# RP5_Right_Flex.net
KiCad netlist of a schematic drawn in Altium Designer
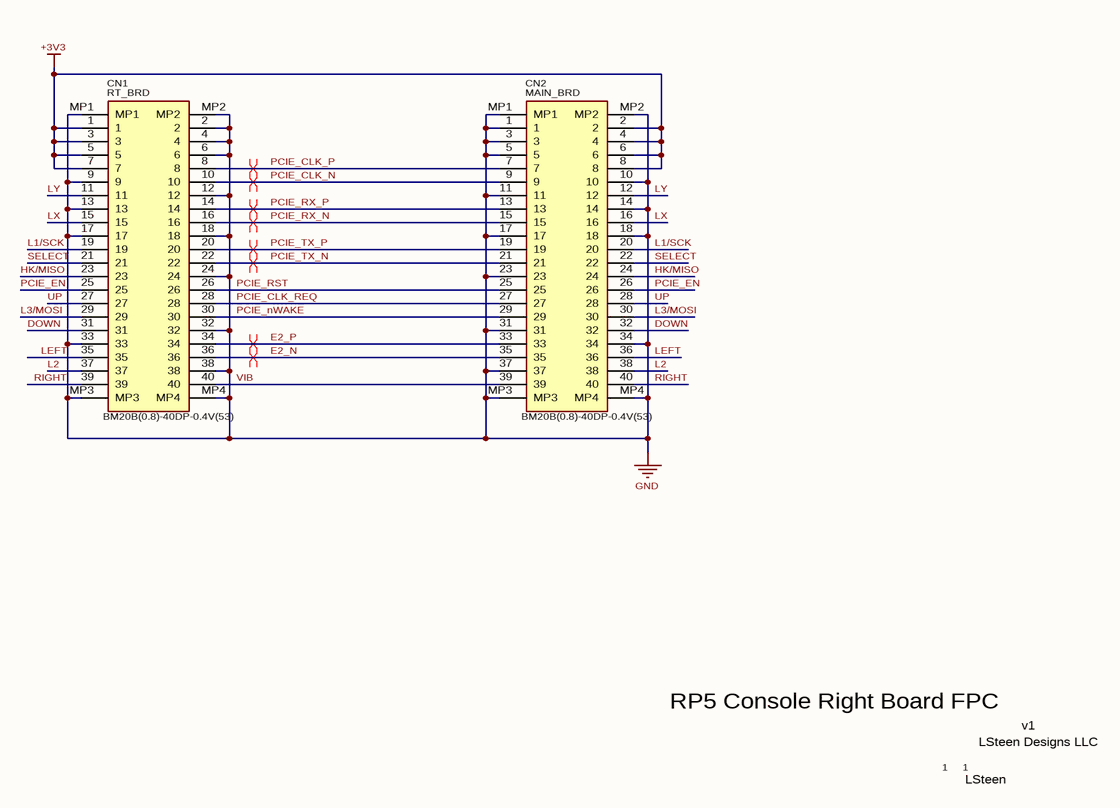
[diagram p0: RP5_Right_Flex.SchDoc]

(export (version "E")
  (design (tool "Eeschema 10.0.6"))
  (components
    (comp (ref "CN1")
      (value "RT_BRD")
      (footprint "BM20B0840DP04V53")
      (description "Connector")
      (fields (field (name "MANUFACTURER_PART_NUMBER") "BM20B(0.8)-40DP-0.4V(51)"))
      (libsource (lib "SamacSys") (part "BM20B(0.8)-40DP-0.4V(53)"))
    )
    (comp (ref "CN2")
      (value "MAIN_BRD")
      (footprint "BM20B0840DP04V53")
      (description "Connector")
      (fields (field (name "MANUFACTURER_PART_NUMBER") "BM20B(0.8)-40DP-0.4V(51)"))
      (libsource (lib "SamacSys") (part "BM20B(0.8)-40DP-0.4V(53)"))
    )
  )
  (nets
    (net (code "1") (name "+3V3") (class "Default")
      (node (ref "CN1") (pin "1") (pinfunction "1_1") (pintype "passive"))
      (node (ref "CN1") (pin "3") (pinfunction "3_3") (pintype "passive"))
      (node (ref "CN1") (pin "5") (pinfunction "5_5") (pintype "passive"))
      (node (ref "CN1") (pin "7") (pinfunction "7_7") (pintype "passive"))
      (node (ref "CN2") (pin "2") (pinfunction "2_2") (pintype "passive"))
      (node (ref "CN2") (pin "4") (pinfunction "4_4") (pintype "passive"))
      (node (ref "CN2") (pin "6") (pinfunction "6_6") (pintype "passive"))
      (node (ref "CN2") (pin "8") (pinfunction "8_8") (pintype "passive"))
    )
    (net (code "2") (name "/DOWN") (class "Default")
      (node (ref "CN1") (pin "31") (pinfunction "31_31") (pintype "passive"))
      (node (ref "CN2") (pin "32") (pinfunction "32_32") (pintype "passive"))
    )
    (net (code "3") (name "/E2_N") (class "Default")
      (node (ref "CN1") (pin "36") (pinfunction "36_36") (pintype "passive"))
      (node (ref "CN2") (pin "35") (pinfunction "35_35") (pintype "passive"))
    )
    (net (code "4") (name "/E2_P") (class "Default")
      (node (ref "CN1") (pin "34") (pinfunction "34_34") (pintype "passive"))
      (node (ref "CN2") (pin "33") (pinfunction "33_33") (pintype "passive"))
    )
    (net (code "5") (name "/HK{slash}MISO") (class "Default")
      (node (ref "CN1") (pin "23") (pinfunction "23_23") (pintype "passive"))
      (node (ref "CN2") (pin "24") (pinfunction "24_24") (pintype "passive"))
    )
    (net (code "6") (name "/L1{slash}SCK") (class "Default")
      (node (ref "CN1") (pin "19") (pinfunction "19_19") (pintype "passive"))
      (node (ref "CN2") (pin "20") (pinfunction "20_20") (pintype "passive"))
    )
    (net (code "7") (name "/L2") (class "Default")
      (node (ref "CN1") (pin "37") (pinfunction "37_37") (pintype "passive"))
      (node (ref "CN2") (pin "38") (pinfunction "38_38") (pintype "passive"))
    )
    (net (code "8") (name "/L3{slash}MOSI") (class "Default")
      (node (ref "CN1") (pin "29") (pinfunction "29_29") (pintype "passive"))
      (node (ref "CN2") (pin "30") (pinfunction "30_30") (pintype "passive"))
    )
    (net (code "9") (name "/LEFT") (class "Default")
      (node (ref "CN1") (pin "35") (pinfunction "35_35") (pintype "passive"))
      (node (ref "CN2") (pin "36") (pinfunction "36_36") (pintype "passive"))
    )
    (net (code "10") (name "/LX") (class "Default")
      (node (ref "CN1") (pin "15") (pinfunction "15_15") (pintype "passive"))
      (node (ref "CN2") (pin "16") (pinfunction "16_16") (pintype "passive"))
    )
    (net (code "11") (name "/LY") (class "Default")
      (node (ref "CN1") (pin "11") (pinfunction "11_11") (pintype "passive"))
      (node (ref "CN2") (pin "12") (pinfunction "12_12") (pintype "passive"))
    )
    (net (code "12") (name "/PCIE_CLK_N") (class "Default")
      (node (ref "CN1") (pin "10") (pinfunction "10_10") (pintype "passive"))
      (node (ref "CN2") (pin "9") (pinfunction "9_9") (pintype "passive"))
    )
    (net (code "13") (name "/PCIE_CLK_P") (class "Default")
      (node (ref "CN1") (pin "8") (pinfunction "8_8") (pintype "passive"))
      (node (ref "CN2") (pin "7") (pinfunction "7_7") (pintype "passive"))
    )
    (net (code "14") (name "/PCIE_CLK_REQ") (class "Default")
      (node (ref "CN1") (pin "28") (pinfunction "28_28") (pintype "passive"))
      (node (ref "CN2") (pin "27") (pinfunction "27_27") (pintype "passive"))
    )
    (net (code "15") (name "/PCIE_EN") (class "Default")
      (node (ref "CN1") (pin "25") (pinfunction "25_25") (pintype "passive"))
      (node (ref "CN2") (pin "26") (pinfunction "26_26") (pintype "passive"))
    )
    (net (code "16") (name "/PCIE_RST") (class "Default")
      (node (ref "CN1") (pin "26") (pinfunction "26_26") (pintype "passive"))
      (node (ref "CN2") (pin "25") (pinfunction "25_25") (pintype "passive"))
    )
    (net (code "17") (name "/PCIE_RX_N") (class "Default")
      (node (ref "CN1") (pin "16") (pinfunction "16_16") (pintype "passive"))
      (node (ref "CN2") (pin "15") (pinfunction "15_15") (pintype "passive"))
    )
    (net (code "18") (name "/PCIE_RX_P") (class "Default")
      (node (ref "CN1") (pin "14") (pinfunction "14_14") (pintype "passive"))
      (node (ref "CN2") (pin "13") (pinfunction "13_13") (pintype "passive"))
    )
    (net (code "19") (name "/PCIE_TX_N") (class "Default")
      (node (ref "CN1") (pin "22") (pinfunction "22_22") (pintype "passive"))
      (node (ref "CN2") (pin "21") (pinfunction "21_21") (pintype "passive"))
    )
    (net (code "20") (name "/PCIE_TX_P") (class "Default")
      (node (ref "CN1") (pin "20") (pinfunction "20_20") (pintype "passive"))
      (node (ref "CN2") (pin "19") (pinfunction "19_19") (pintype "passive"))
    )
    (net (code "21") (name "/PCIE_nWAKE") (class "Default")
      (node (ref "CN1") (pin "30") (pinfunction "30_30") (pintype "passive"))
      (node (ref "CN2") (pin "29") (pinfunction "29_29") (pintype "passive"))
    )
    (net (code "22") (name "/RIGHT") (class "Default")
      (node (ref "CN1") (pin "39") (pinfunction "39_39") (pintype "passive"))
      (node (ref "CN2") (pin "40") (pinfunction "40_40") (pintype "passive"))
    )
    (net (code "23") (name "/SELECT") (class "Default")
      (node (ref "CN1") (pin "21") (pinfunction "21_21") (pintype "passive"))
      (node (ref "CN2") (pin "22") (pinfunction "22_22") (pintype "passive"))
    )
    (net (code "24") (name "/UP") (class "Default")
      (node (ref "CN1") (pin "27") (pinfunction "27_27") (pintype "passive"))
      (node (ref "CN2") (pin "28") (pinfunction "28_28") (pintype "passive"))
    )
    (net (code "25") (name "/VIB") (class "Default")
      (node (ref "CN1") (pin "40") (pinfunction "40_40") (pintype "passive"))
      (node (ref "CN2") (pin "39") (pinfunction "39_39") (pintype "passive"))
    )
    (net (code "26") (name "GND") (class "Default")
      (node (ref "CN1") (pin "12") (pinfunction "12_12") (pintype "passive"))
      (node (ref "CN1") (pin "13") (pinfunction "13_13") (pintype "passive"))
      (node (ref "CN1") (pin "17") (pinfunction "17_17") (pintype "passive"))
      (node (ref "CN1") (pin "18") (pinfunction "18_18") (pintype "passive"))
      (node (ref "CN1") (pin "2") (pinfunction "2_2") (pintype "passive"))
      (node (ref "CN1") (pin "24") (pinfunction "24_24") (pintype "passive"))
      (node (ref "CN1") (pin "32") (pinfunction "32_32") (pintype "passive"))
      (node (ref "CN1") (pin "33") (pinfunction "33_33") (pintype "passive"))
      (node (ref "CN1") (pin "38") (pinfunction "38_38") (pintype "passive"))
      (node (ref "CN1") (pin "4") (pinfunction "4_4") (pintype "passive"))
      (node (ref "CN1") (pin "6") (pinfunction "6_6") (pintype "passive"))
      (node (ref "CN1") (pin "9") (pinfunction "9_9") (pintype "passive"))
      (node (ref "CN1") (pin "MP1") (pinfunction "MP1_MP1") (pintype "passive"))
      (node (ref "CN1") (pin "MP2") (pinfunction "MP2_MP2") (pintype "passive"))
      (node (ref "CN1") (pin "MP3") (pinfunction "MP3_MP3") (pintype "passive"))
      (node (ref "CN1") (pin "MP4") (pinfunction "MP4_MP4") (pintype "passive"))
      (node (ref "CN2") (pin "1") (pinfunction "1_1") (pintype "passive"))
      (node (ref "CN2") (pin "10") (pinfunction "10_10") (pintype "passive"))
      (node (ref "CN2") (pin "11") (pinfunction "11_11") (pintype "passive"))
      (node (ref "CN2") (pin "14") (pinfunction "14_14") (pintype "passive"))
      (node (ref "CN2") (pin "17") (pinfunction "17_17") (pintype "passive"))
      (node (ref "CN2") (pin "18") (pinfunction "18_18") (pintype "passive"))
      (node (ref "CN2") (pin "23") (pinfunction "23_23") (pintype "passive"))
      (node (ref "CN2") (pin "3") (pinfunction "3_3") (pintype "passive"))
      (node (ref "CN2") (pin "31") (pinfunction "31_31") (pintype "passive"))
      (node (ref "CN2") (pin "34") (pinfunction "34_34") (pintype "passive"))
      (node (ref "CN2") (pin "37") (pinfunction "37_37") (pintype "passive"))
      (node (ref "CN2") (pin "5") (pinfunction "5_5") (pintype "passive"))
      (node (ref "CN2") (pin "MP1") (pinfunction "MP1_MP1") (pintype "passive"))
      (node (ref "CN2") (pin "MP2") (pinfunction "MP2_MP2") (pintype "passive"))
      (node (ref "CN2") (pin "MP3") (pinfunction "MP3_MP3") (pintype "passive"))
      (node (ref "CN2") (pin "MP4") (pinfunction "MP4_MP4") (pintype "passive"))
    )
  )
)
